# 8channelrelaydriver_smd.net
KiCad netlist of a schematic drawn in EAGLE
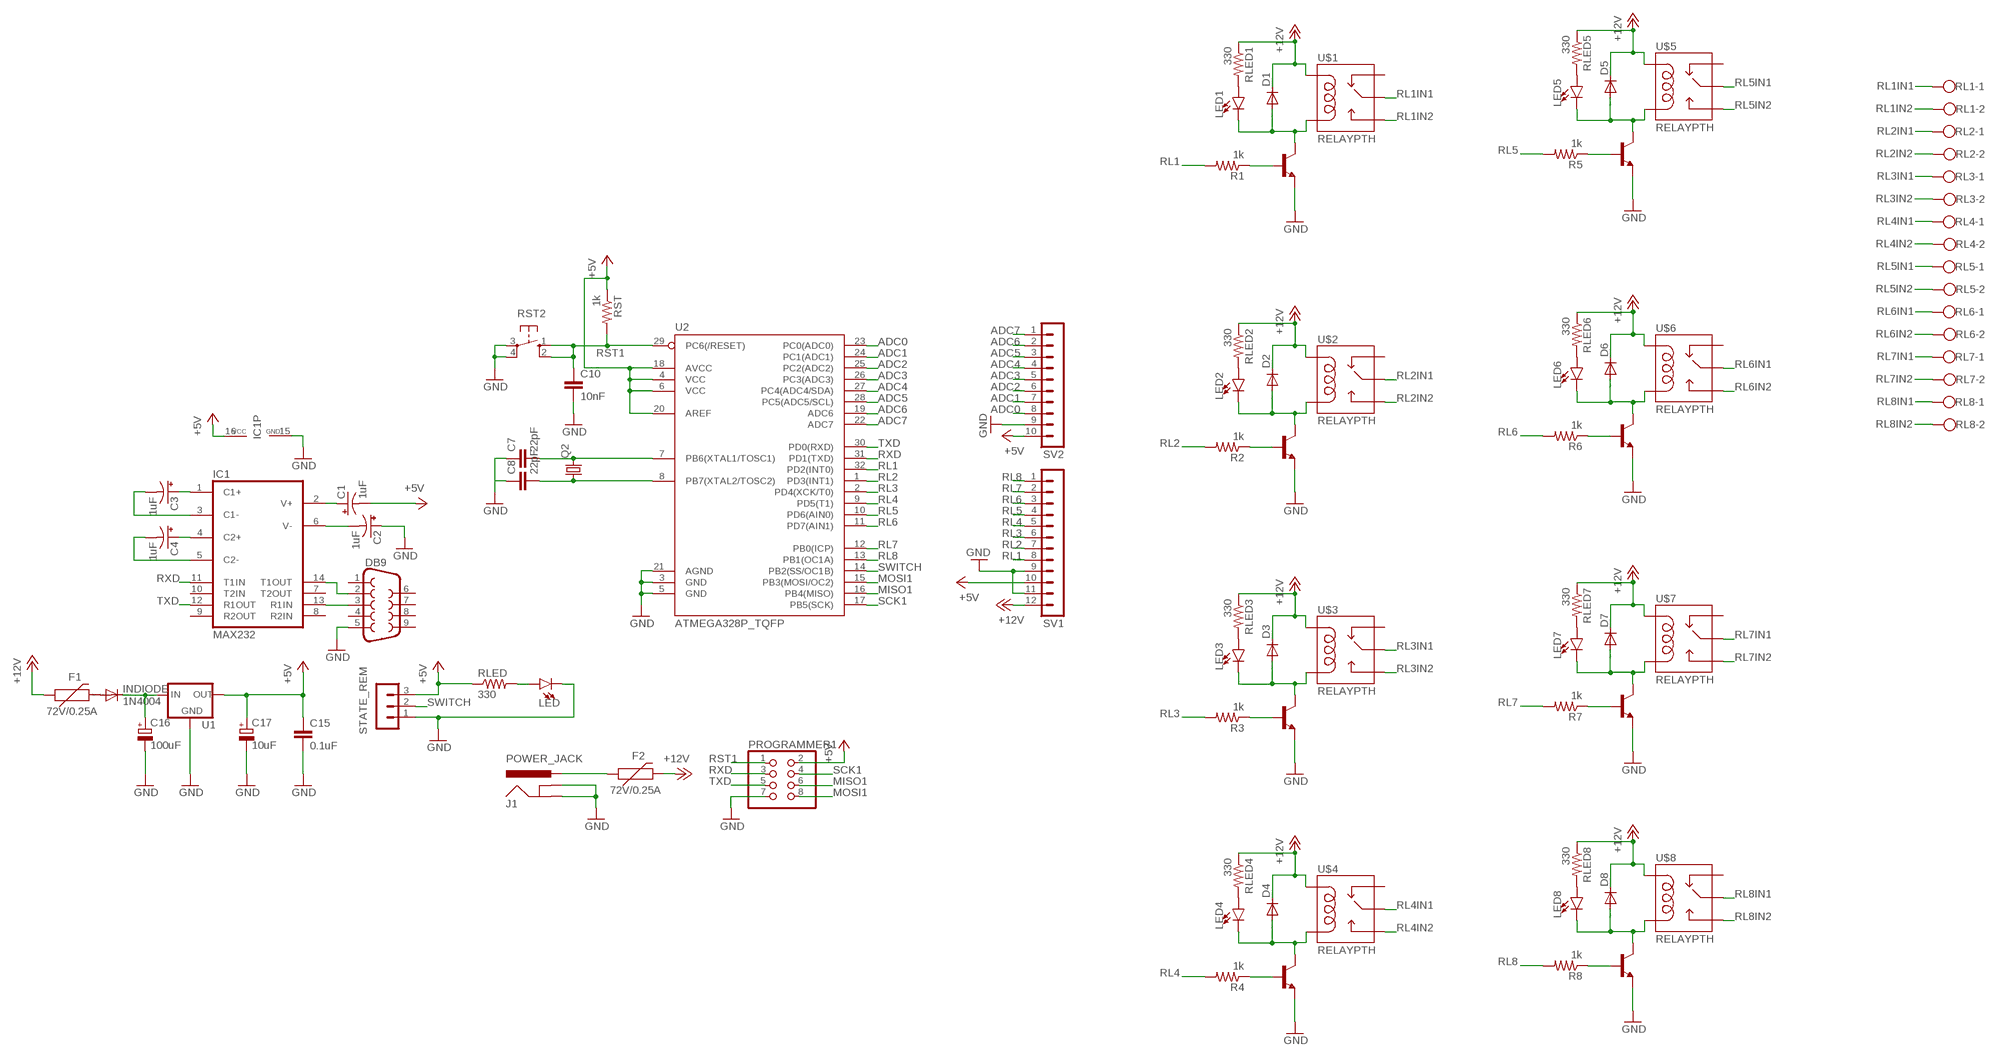
[diagram p0: schematic, sheet 1]

(export (version "E")
  (design (tool "Eeschema 10.0.6"))
  (components
    (comp (ref "C1")
      (value "1uF")
      (footprint "eagle-import:E2,5-6")
      (libsource (lib "eagle-import") (part "CPOL-USE2.5-6"))
    )
    (comp (ref "C2")
      (value "1uF")
      (footprint "eagle-import:E2,5-6")
      (libsource (lib "eagle-import") (part "CPOL-USE2.5-6"))
    )
    (comp (ref "C3")
      (value "1uF")
      (footprint "eagle-import:E2,5-6")
      (libsource (lib "eagle-import") (part "CPOL-USE2.5-6"))
    )
    (comp (ref "C4")
      (value "1uF")
      (footprint "eagle-import:E2,5-6")
      (libsource (lib "eagle-import") (part "CPOL-USE2.5-6"))
    )
    (comp (ref "C7")
      (value "22pF")
      (footprint "eagle-import:C1206")
      (libsource (lib "eagle-import") (part "C-EUC1206"))
    )
    (comp (ref "C8")
      (value "22pF")
      (footprint "eagle-import:C1206")
      (libsource (lib "eagle-import") (part "C-EUC1206"))
    )
    (comp (ref "C10")
      (value "10nF")
      (footprint "eagle-import:C1206")
      (libsource (lib "eagle-import") (part "C-EUC1206"))
    )
    (comp (ref "C15")
      (value "0.1uF")
      (footprint "eagle-import:C1206")
      (libsource (lib "eagle-import") (part "C-EUC1206"))
    )
    (comp (ref "C16")
      (value "100uF")
      (footprint "eagle-import:E2,5-6")
      (libsource (lib "eagle-import") (part "CPOL-EUE2.5-6"))
    )
    (comp (ref "C17")
      (value "10uF")
      (footprint "eagle-import:E2,5-6")
      (libsource (lib "eagle-import") (part "CPOL-EUE2.5-6"))
    )
    (comp (ref "D1")
      (value "1N4004")
      (footprint "eagle-import:DO41-10")
      (libsource (lib "eagle-import") (part "1N4004"))
    )
    (comp (ref "D2")
      (value "1N4004")
      (footprint "eagle-import:DO41-10")
      (libsource (lib "eagle-import") (part "1N4004"))
    )
    (comp (ref "D3")
      (value "1N4004")
      (footprint "eagle-import:DO41-10")
      (libsource (lib "eagle-import") (part "1N4004"))
    )
    (comp (ref "D4")
      (value "1N4004")
      (footprint "eagle-import:DO41-10")
      (libsource (lib "eagle-import") (part "1N4004"))
    )
    (comp (ref "D5")
      (value "1N4004")
      (footprint "eagle-import:DO41-10")
      (libsource (lib "eagle-import") (part "1N4004"))
    )
    (comp (ref "D6")
      (value "1N4004")
      (footprint "eagle-import:DO41-10")
      (libsource (lib "eagle-import") (part "1N4004"))
    )
    (comp (ref "D7")
      (value "1N4004")
      (footprint "eagle-import:DO41-10")
      (libsource (lib "eagle-import") (part "1N4004"))
    )
    (comp (ref "D8")
      (value "1N4004")
      (footprint "eagle-import:DO41-10")
      (libsource (lib "eagle-import") (part "1N4004"))
    )
    (comp (ref "DB9")
      (value "DB9FEMALE")
      (footprint "eagle-import:DB9")
      (libsource (lib "eagle-import") (part "DB9FEMALE"))
    )
    (comp (ref "F1")
      (value "72V/0.25A")
      (footprint "eagle-import:PTH")
      (libsource (lib "eagle-import") (part "PPTC_PTH"))
    )
    (comp (ref "F2")
      (value "72V/0.25A")
      (footprint "eagle-import:PTH")
      (libsource (lib "eagle-import") (part "PPTC_PTH"))
    )
    (comp (ref "IC1")
      (value "MAX232")
      (footprint "eagle-import:DIL16")
      (fields (field (name "MF") "MAXIM") (field (name "MPN") "MAX232ACPE+"))
      (libsource (lib "eagle-import") (part "MAX232"))
    )
    (comp (ref "INDIODE")
      (value "1N4004")
      (footprint "eagle-import:DO41-10")
      (libsource (lib "eagle-import") (part "1N4004"))
    )
    (comp (ref "J1")
      (value "POWER_JACK")
      (footprint "eagle-import:POWER_JACK_PTH")
      (libsource (lib "eagle-import") (part "POWER_JACK"))
    )
    (comp (ref "LED")
      (value "LED5MM")
      (footprint "eagle-import:LED_5MM")
      (libsource (lib "eagle-import") (part "LED5MM"))
    )
    (comp (ref "LED1")
      (value "LED5MM")
      (footprint "eagle-import:LED_5MM")
      (libsource (lib "eagle-import") (part "LED5MM"))
    )
    (comp (ref "LED2")
      (value "LED5MM")
      (footprint "eagle-import:LED_5MM")
      (libsource (lib "eagle-import") (part "LED5MM"))
    )
    (comp (ref "LED3")
      (value "LED5MM")
      (footprint "eagle-import:LED_5MM")
      (libsource (lib "eagle-import") (part "LED5MM"))
    )
    (comp (ref "LED4")
      (value "LED5MM")
      (footprint "eagle-import:LED_5MM")
      (libsource (lib "eagle-import") (part "LED5MM"))
    )
    (comp (ref "LED5")
      (value "LED5MM")
      (footprint "eagle-import:LED_5MM")
      (libsource (lib "eagle-import") (part "LED5MM"))
    )
    (comp (ref "LED6")
      (value "LED5MM")
      (footprint "eagle-import:LED_5MM")
      (libsource (lib "eagle-import") (part "LED5MM"))
    )
    (comp (ref "LED7")
      (value "LED5MM")
      (footprint "eagle-import:LED_5MM")
      (libsource (lib "eagle-import") (part "LED5MM"))
    )
    (comp (ref "LED8")
      (value "LED5MM")
      (footprint "eagle-import:LED_5MM")
      (libsource (lib "eagle-import") (part "LED5MM"))
    )
    (comp (ref "PROGRAMMER1")
      (value "PINHD-2X4")
      (footprint "eagle-import:2X04")
      (libsource (lib "eagle-import") (part "PINHD-2X4"))
    )
    (comp (ref "Q2")
      (value "CRYSTALHC49U70")
      (footprint "eagle-import:HC49U70")
      (libsource (lib "eagle-import") (part "CRYSTALHC49U70"))
    )
    (comp (ref "R1")
      (value "1k")
      (footprint "eagle-import:M1206")
      (libsource (lib "eagle-import") (part "R-US_M1206"))
    )
    (comp (ref "R2")
      (value "1k")
      (footprint "eagle-import:M1206")
      (libsource (lib "eagle-import") (part "R-US_M1206"))
    )
    (comp (ref "R3")
      (value "1k")
      (footprint "eagle-import:M1206")
      (libsource (lib "eagle-import") (part "R-US_M1206"))
    )
    (comp (ref "R4")
      (value "1k")
      (footprint "eagle-import:M1206")
      (libsource (lib "eagle-import") (part "R-US_M1206"))
    )
    (comp (ref "R5")
      (value "1k")
      (footprint "eagle-import:M1206")
      (libsource (lib "eagle-import") (part "R-US_M1206"))
    )
    (comp (ref "R6")
      (value "1k")
      (footprint "eagle-import:M1206")
      (libsource (lib "eagle-import") (part "R-US_M1206"))
    )
    (comp (ref "R7")
      (value "1k")
      (footprint "eagle-import:M1206")
      (libsource (lib "eagle-import") (part "R-US_M1206"))
    )
    (comp (ref "R8")
      (value "1k")
      (footprint "eagle-import:M1206")
      (libsource (lib "eagle-import") (part "R-US_M1206"))
    )
    (comp (ref "RL1")
      (value "W237-102")
      (footprint "eagle-import:W237-102")
      (fields (field (name "MPN") "237-102"))
      (libsource (lib "eagle-import") (part "W237-102"))
    )
    (comp (ref "RL2")
      (value "W237-102")
      (footprint "eagle-import:W237-102")
      (fields (field (name "MPN") "237-102"))
      (libsource (lib "eagle-import") (part "W237-102"))
    )
    (comp (ref "RL3")
      (value "W237-102")
      (footprint "eagle-import:W237-102")
      (fields (field (name "MPN") "237-102"))
      (libsource (lib "eagle-import") (part "W237-102"))
    )
    (comp (ref "RL4")
      (value "W237-102")
      (footprint "eagle-import:W237-102")
      (fields (field (name "MPN") "237-102"))
      (libsource (lib "eagle-import") (part "W237-102"))
    )
    (comp (ref "RL5")
      (value "W237-102")
      (footprint "eagle-import:W237-102")
      (fields (field (name "MPN") "237-102"))
      (libsource (lib "eagle-import") (part "W237-102"))
    )
    (comp (ref "RL6")
      (value "W237-102")
      (footprint "eagle-import:W237-102")
      (fields (field (name "MPN") "237-102"))
      (libsource (lib "eagle-import") (part "W237-102"))
    )
    (comp (ref "RL7")
      (value "W237-102")
      (footprint "eagle-import:W237-102")
      (fields (field (name "MPN") "237-102"))
      (libsource (lib "eagle-import") (part "W237-102"))
    )
    (comp (ref "RL8")
      (value "W237-102")
      (footprint "eagle-import:W237-102")
      (fields (field (name "MPN") "237-102"))
      (libsource (lib "eagle-import") (part "W237-102"))
    )
    (comp (ref "RLED")
      (value "330")
      (footprint "eagle-import:M1206")
      (libsource (lib "eagle-import") (part "R-US_M1206"))
    )
    (comp (ref "RLED1")
      (value "330")
      (footprint "eagle-import:M1206")
      (libsource (lib "eagle-import") (part "R-US_M1206"))
    )
    (comp (ref "RLED2")
      (value "330")
      (footprint "eagle-import:M1206")
      (libsource (lib "eagle-import") (part "R-US_M1206"))
    )
    (comp (ref "RLED3")
      (value "330")
      (footprint "eagle-import:M1206")
      (libsource (lib "eagle-import") (part "R-US_M1206"))
    )
    (comp (ref "RLED4")
      (value "330")
      (footprint "eagle-import:M1206")
      (libsource (lib "eagle-import") (part "R-US_M1206"))
    )
    (comp (ref "RLED5")
      (value "330")
      (footprint "eagle-import:M1206")
      (libsource (lib "eagle-import") (part "R-US_M1206"))
    )
    (comp (ref "RLED6")
      (value "330")
      (footprint "eagle-import:M1206")
      (libsource (lib "eagle-import") (part "R-US_M1206"))
    )
    (comp (ref "RLED7")
      (value "330")
      (footprint "eagle-import:M1206")
      (libsource (lib "eagle-import") (part "R-US_M1206"))
    )
    (comp (ref "RLED8")
      (value "330")
      (footprint "eagle-import:M1206")
      (libsource (lib "eagle-import") (part "R-US_M1206"))
    )
    (comp (ref "RST")
      (value "1k")
      (footprint "eagle-import:M1206")
      (libsource (lib "eagle-import") (part "R-US_M1206"))
    )
    (comp (ref "RST2")
      (value "10-XX")
      (footprint "eagle-import:B3F-10XX")
      (fields (field (name "MPN") "B3F-1000"))
      (libsource (lib "eagle-import") (part "10-XX"))
    )
    (comp (ref "STATE_REM")
      (value "MA03-1")
      (footprint "eagle-import:MA03-1")
      (libsource (lib "eagle-import") (part "MA03-1"))
    )
    (comp (ref "SV1")
      (value "MA12-1")
      (footprint "eagle-import:MA12-1")
      (libsource (lib "eagle-import") (part "MA12-1"))
    )
    (comp (ref "SV2")
      (value "MA10-1")
      (footprint "eagle-import:MA10-1")
      (libsource (lib "eagle-import") (part "MA10-1"))
    )
    (comp (ref "T1")
      (value "BC847")
      (footprint "eagle-import:SOT23")
      (libsource (lib "eagle-import") (part "BC847"))
    )
    (comp (ref "T2")
      (value "BC847")
      (footprint "eagle-import:SOT23")
      (libsource (lib "eagle-import") (part "BC847"))
    )
    (comp (ref "T3")
      (value "BC847")
      (footprint "eagle-import:SOT23")
      (libsource (lib "eagle-import") (part "BC847"))
    )
    (comp (ref "T4")
      (value "BC847")
      (footprint "eagle-import:SOT23")
      (libsource (lib "eagle-import") (part "BC847"))
    )
    (comp (ref "T5")
      (value "BC847")
      (footprint "eagle-import:SOT23")
      (libsource (lib "eagle-import") (part "BC847"))
    )
    (comp (ref "T6")
      (value "BC847")
      (footprint "eagle-import:SOT23")
      (libsource (lib "eagle-import") (part "BC847"))
    )
    (comp (ref "T7")
      (value "BC847")
      (footprint "eagle-import:SOT23")
      (libsource (lib "eagle-import") (part "BC847"))
    )
    (comp (ref "T8")
      (value "BC847")
      (footprint "eagle-import:SOT23")
      (libsource (lib "eagle-import") (part "BC847"))
    )
    (comp (ref "U$1")
      (value "RELAYPTH")
      (footprint "eagle-import:SRD-05VDC-SL-C")
      (libsource (lib "eagle-import") (part "RELAYPTH"))
    )
    (comp (ref "U$2")
      (value "RELAYPTH")
      (footprint "eagle-import:SRD-05VDC-SL-C")
      (libsource (lib "eagle-import") (part "RELAYPTH"))
    )
    (comp (ref "U$3")
      (value "RELAYPTH")
      (footprint "eagle-import:SRD-05VDC-SL-C")
      (libsource (lib "eagle-import") (part "RELAYPTH"))
    )
    (comp (ref "U$4")
      (value "RELAYPTH")
      (footprint "eagle-import:SRD-05VDC-SL-C")
      (libsource (lib "eagle-import") (part "RELAYPTH"))
    )
    (comp (ref "U$5")
      (value "RELAYPTH")
      (footprint "eagle-import:SRD-05VDC-SL-C")
      (libsource (lib "eagle-import") (part "RELAYPTH"))
    )
    (comp (ref "U$6")
      (value "RELAYPTH")
      (footprint "eagle-import:SRD-05VDC-SL-C")
      (libsource (lib "eagle-import") (part "RELAYPTH"))
    )
    (comp (ref "U$7")
      (value "RELAYPTH")
      (footprint "eagle-import:SRD-05VDC-SL-C")
      (libsource (lib "eagle-import") (part "RELAYPTH"))
    )
    (comp (ref "U$8")
      (value "RELAYPTH")
      (footprint "eagle-import:SRD-05VDC-SL-C")
      (libsource (lib "eagle-import") (part "RELAYPTH"))
    )
    (comp (ref "U1")
      (value "V_REG_78XXSIDE")
      (footprint "eagle-import:78XXL")
      (libsource (lib "eagle-import") (part "V_REG_78XXSIDE"))
    )
    (comp (ref "U2")
      (value "ATMEGA328P_TQFP")
      (footprint "eagle-import:TQFP32-08")
      (libsource (lib "eagle-import") (part "ATMEGA328P_TQFP"))
    )
  )
  (nets
    (net (code "1") (name "+5V") (class "Default")
      (node (ref "C1") (pin "-") (pinfunction "-_-") (pintype "passive"))
      (node (ref "C15") (pin "1") (pinfunction "1_1") (pintype "passive"))
      (node (ref "C17") (pin "+") (pinfunction "+_+") (pintype "passive"))
      (node (ref "IC1") (pin "16") (pinfunction "VCC_16") (pintype "power_in"))
      (node (ref "PROGRAMMER1") (pin "2") (pinfunction "2_2") (pintype "passive"))
      (node (ref "RLED") (pin "1") (pinfunction "1_1") (pintype "passive"))
      (node (ref "RST") (pin "1") (pinfunction "1_1") (pintype "passive"))
      (node (ref "STATE_REM") (pin "3") (pinfunction "3_3") (pintype "passive"))
      (node (ref "SV1") (pin "10") (pinfunction "10_10") (pintype "passive"))
      (node (ref "SV2") (pin "10") (pinfunction "10_10") (pintype "passive"))
      (node (ref "U1") (pin "OUT") (pinfunction "OUT_OUT") (pintype "passive"))
      (node (ref "U2") (pin "18") (pinfunction "AVCC_18") (pintype "bidirectional"))
      (node (ref "U2") (pin "20") (pinfunction "AREF_20") (pintype "bidirectional"))
      (node (ref "U2") (pin "4") (pinfunction "VCC_4") (pintype "bidirectional"))
      (node (ref "U2") (pin "6") (pinfunction "VCC_6") (pintype "bidirectional"))
    )
    (net (code "2") (name "+12V") (class "Default")
      (node (ref "D1") (pin "C") (pinfunction "C_C") (pintype "passive"))
      (node (ref "D2") (pin "C") (pinfunction "C_C") (pintype "passive"))
      (node (ref "D3") (pin "C") (pinfunction "C_C") (pintype "passive"))
      (node (ref "D4") (pin "C") (pinfunction "C_C") (pintype "passive"))
      (node (ref "D5") (pin "C") (pinfunction "C_C") (pintype "passive"))
      (node (ref "D6") (pin "C") (pinfunction "C_C") (pintype "passive"))
      (node (ref "D7") (pin "C") (pinfunction "C_C") (pintype "passive"))
      (node (ref "D8") (pin "C") (pinfunction "C_C") (pintype "passive"))
      (node (ref "F1") (pin "P$1") (pinfunction "1_P$1") (pintype "bidirectional"))
      (node (ref "F2") (pin "P$2") (pinfunction "2_P$2") (pintype "bidirectional"))
      (node (ref "RLED1") (pin "1") (pinfunction "1_1") (pintype "passive"))
      (node (ref "RLED2") (pin "1") (pinfunction "1_1") (pintype "passive"))
      (node (ref "RLED3") (pin "1") (pinfunction "1_1") (pintype "passive"))
      (node (ref "RLED4") (pin "1") (pinfunction "1_1") (pintype "passive"))
      (node (ref "RLED5") (pin "1") (pinfunction "1_1") (pintype "passive"))
      (node (ref "RLED6") (pin "1") (pinfunction "1_1") (pintype "passive"))
      (node (ref "RLED7") (pin "1") (pinfunction "1_1") (pintype "passive"))
      (node (ref "RLED8") (pin "1") (pinfunction "1_1") (pintype "passive"))
      (node (ref "SV1") (pin "12") (pinfunction "12_12") (pintype "passive"))
      (node (ref "U$1") (pin "COIL1") (pinfunction "COIL1_COIL1") (pintype "bidirectional"))
      (node (ref "U$2") (pin "COIL1") (pinfunction "COIL1_COIL1") (pintype "bidirectional"))
      (node (ref "U$3") (pin "COIL1") (pinfunction "COIL1_COIL1") (pintype "bidirectional"))
      (node (ref "U$4") (pin "COIL1") (pinfunction "COIL1_COIL1") (pintype "bidirectional"))
      (node (ref "U$5") (pin "COIL1") (pinfunction "COIL1_COIL1") (pintype "bidirectional"))
      (node (ref "U$6") (pin "COIL1") (pinfunction "COIL1_COIL1") (pintype "bidirectional"))
      (node (ref "U$7") (pin "COIL1") (pinfunction "COIL1_COIL1") (pintype "bidirectional"))
      (node (ref "U$8") (pin "COIL1") (pinfunction "COIL1_COIL1") (pintype "bidirectional"))
    )
    (net (code "3") (name "/ADC0") (class "Default")
      (node (ref "SV2") (pin "8") (pinfunction "8_8") (pintype "passive"))
      (node (ref "U2") (pin "23") (pinfunction "PC0(ADC0)_23") (pintype "bidirectional"))
    )
    (net (code "4") (name "/ADC1") (class "Default")
      (node (ref "SV2") (pin "7") (pinfunction "7_7") (pintype "passive"))
      (node (ref "U2") (pin "24") (pinfunction "PC1(ADC1)_24") (pintype "bidirectional"))
    )
    (net (code "5") (name "/ADC2") (class "Default")
      (node (ref "SV2") (pin "6") (pinfunction "6_6") (pintype "passive"))
      (node (ref "U2") (pin "25") (pinfunction "PC2(ADC2)_25") (pintype "bidirectional"))
    )
    (net (code "6") (name "/ADC3") (class "Default")
      (node (ref "SV2") (pin "5") (pinfunction "5_5") (pintype "passive"))
      (node (ref "U2") (pin "26") (pinfunction "PC3(ADC3)_26") (pintype "bidirectional"))
    )
    (net (code "7") (name "/ADC4") (class "Default")
      (node (ref "SV2") (pin "4") (pinfunction "4_4") (pintype "passive"))
      (node (ref "U2") (pin "27") (pinfunction "PC4(ADC4/SDA)_27") (pintype "bidirectional"))
    )
    (net (code "8") (name "/ADC5") (class "Default")
      (node (ref "SV2") (pin "3") (pinfunction "3_3") (pintype "passive"))
      (node (ref "U2") (pin "28") (pinfunction "PC5(ADC5/SCL)_28") (pintype "bidirectional"))
    )
    (net (code "9") (name "/ADC6") (class "Default")
      (node (ref "SV2") (pin "2") (pinfunction "2_2") (pintype "passive"))
      (node (ref "U2") (pin "19") (pinfunction "ADC6_19") (pintype "bidirectional"))
    )
    (net (code "10") (name "/ADC7") (class "Default")
      (node (ref "SV2") (pin "1") (pinfunction "1_1") (pintype "passive"))
      (node (ref "U2") (pin "22") (pinfunction "ADC7_22") (pintype "bidirectional"))
    )
    (net (code "11") (name "/MISO1") (class "Default")
      (node (ref "PROGRAMMER1") (pin "6") (pinfunction "6_6") (pintype "passive"))
      (node (ref "U2") (pin "16") (pinfunction "PB4(MISO)_16") (pintype "bidirectional"))
    )
    (net (code "12") (name "/MOSI1") (class "Default")
      (node (ref "PROGRAMMER1") (pin "8") (pinfunction "8_8") (pintype "passive"))
      (node (ref "U2") (pin "15") (pinfunction "PB3(MOSI/OC2)_15") (pintype "bidirectional"))
    )
    (net (code "13") (name "/RL1") (class "Default")
      (node (ref "R1") (pin "2") (pinfunction "2_2") (pintype "passive"))
      (node (ref "SV1") (pin "8") (pinfunction "8_8") (pintype "passive"))
      (node (ref "U2") (pin "32") (pinfunction "PD2(INT0)_32") (pintype "bidirectional"))
    )
    (net (code "14") (name "/RL1IN1") (class "Default")
      (node (ref "RL1") (pin "1") (pinfunction "KL_1") (pintype "passive"))
      (node (ref "U$1") (pin "SWCOMMON") (pinfunction "SWCOMMON_SWCOMMON") (pintype "bidirectional"))
    )
    (net (code "15") (name "/RL1IN2") (class "Default")
      (node (ref "RL1") (pin "2") (pinfunction "KL_2") (pintype "passive"))
      (node (ref "U$1") (pin "SWOPEN") (pinfunction "SWOPEN_SWOPEN") (pintype "bidirectional"))
    )
    (net (code "16") (name "/RL2") (class "Default")
      (node (ref "R2") (pin "2") (pinfunction "2_2") (pintype "passive"))
      (node (ref "SV1") (pin "7") (pinfunction "7_7") (pintype "passive"))
      (node (ref "U2") (pin "1") (pinfunction "PD3(INT1)_1") (pintype "bidirectional"))
    )
    (net (code "17") (name "/RL2IN1") (class "Default")
      (node (ref "RL2") (pin "1") (pinfunction "KL_1") (pintype "passive"))
      (node (ref "U$2") (pin "SWCOMMON") (pinfunction "SWCOMMON_SWCOMMON") (pintype "bidirectional"))
    )
    (net (code "18") (name "/RL2IN2") (class "Default")
      (node (ref "RL2") (pin "2") (pinfunction "KL_2") (pintype "passive"))
      (node (ref "U$2") (pin "SWOPEN") (pinfunction "SWOPEN_SWOPEN") (pintype "bidirectional"))
    )
    (net (code "19") (name "/RL3") (class "Default")
      (node (ref "R3") (pin "2") (pinfunction "2_2") (pintype "passive"))
      (node (ref "SV1") (pin "6") (pinfunction "6_6") (pintype "passive"))
      (node (ref "U2") (pin "2") (pinfunction "PD4(XCK/T0)_2") (pintype "bidirectional"))
    )
    (net (code "20") (name "/RL3IN1") (class "Default")
      (node (ref "RL3") (pin "1") (pinfunction "KL_1") (pintype "passive"))
      (node (ref "U$3") (pin "SWCOMMON") (pinfunction "SWCOMMON_SWCOMMON") (pintype "bidirectional"))
    )
    (net (code "21") (name "/RL3IN2") (class "Default")
      (node (ref "RL3") (pin "2") (pinfunction "KL_2") (pintype "passive"))
      (node (ref "U$3") (pin "SWOPEN") (pinfunction "SWOPEN_SWOPEN") (pintype "bidirectional"))
    )
    (net (code "22") (name "/RL4") (class "Default")
      (node (ref "R4") (pin "2") (pinfunction "2_2") (pintype "passive"))
      (node (ref "SV1") (pin "5") (pinfunction "5_5") (pintype "passive"))
      (node (ref "U2") (pin "9") (pinfunction "PD5(T1)_9") (pintype "bidirectional"))
    )
    (net (code "23") (name "/RL4IN1") (class "Default")
      (node (ref "RL4") (pin "1") (pinfunction "KL_1") (pintype "passive"))
      (node (ref "U$4") (pin "SWCOMMON") (pinfunction "SWCOMMON_SWCOMMON") (pintype "bidirectional"))
    )
    (net (code "24") (name "/RL4IN2") (class "Default")
      (node (ref "RL4") (pin "2") (pinfunction "KL_2") (pintype "passive"))
      (node (ref "U$4") (pin "SWOPEN") (pinfunction "SWOPEN_SWOPEN") (pintype "bidirectional"))
    )
    (net (code "25") (name "/RL5") (class "Default")
      (node (ref "R5") (pin "2") (pinfunction "2_2") (pintype "passive"))
      (node (ref "SV1") (pin "4") (pinfunction "4_4") (pintype "passive"))
      (node (ref "U2") (pin "10") (pinfunction "PD6(AIN0)_10") (pintype "bidirectional"))
    )
    (net (code "26") (name "/RL5IN1") (class "Default")
      (node (ref "RL5") (pin "1") (pinfunction "KL_1") (pintype "passive"))
      (node (ref "U$5") (pin "SWCOMMON") (pinfunction "SWCOMMON_SWCOMMON") (pintype "bidirectional"))
    )
    (net (code "27") (name "/RL5IN2") (class "Default")
      (node (ref "RL5") (pin "2") (pinfunction "KL_2") (pintype "passive"))
      (node (ref "U$5") (pin "SWOPEN") (pinfunction "SWOPEN_SWOPEN") (pintype "bidirectional"))
    )
    (net (code "28") (name "/RL6") (class "Default")
      (node (ref "R6") (pin "2") (pinfunction "2_2") (pintype "passive"))
      (node (ref "SV1") (pin "3") (pinfunction "3_3") (pintype "passive"))
      (node (ref "U2") (pin "11") (pinfunction "PD7(AIN1)_11") (pintype "bidirectional"))
    )
    (net (code "29") (name "/RL6IN1") (class "Default")
      (node (ref "RL6") (pin "1") (pinfunction "KL_1") (pintype "passive"))
      (node (ref "U$6") (pin "SWCOMMON") (pinfunction "SWCOMMON_SWCOMMON") (pintype "bidirectional"))
    )
    (net (code "30") (name "/RL6IN2") (class "Default")
      (node (ref "RL6") (pin "2") (pinfunction "KL_2") (pintype "passive"))
      (node (ref "U$6") (pin "SWOPEN") (pinfunction "SWOPEN_SWOPEN") (pintype "bidirectional"))
    )
    (net (code "31") (name "/RL7") (class "Default")
      (node (ref "R7") (pin "2") (pinfunction "2_2") (pintype "passive"))
      (node (ref "SV1") (pin "2") (pinfunction "2_2") (pintype "passive"))
      (node (ref "U2") (pin "12") (pinfunction "PB0(ICP)_12") (pintype "bidirectional"))
    )
    (net (code "32") (name "/RL7IN1") (class "Default")
      (node (ref "RL7") (pin "1") (pinfunction "KL_1") (pintype "passive"))
      (node (ref "U$7") (pin "SWCOMMON") (pinfunction "SWCOMMON_SWCOMMON") (pintype "bidirectional"))
    )
    (net (code "33") (name "/RL7IN2") (class "Default")
      (node (ref "RL7") (pin "2") (pinfunction "KL_2") (pintype "passive"))
      (node (ref "U$7") (pin "SWOPEN") (pinfunction "SWOPEN_SWOPEN") (pintype "bidirectional"))
    )
    (net (code "34") (name "/RL8") (class "Default")
      (node (ref "R8") (pin "2") (pinfunction "2_2") (pintype "passive"))
      (node (ref "SV1") (pin "1") (pinfunction "1_1") (pintype "passive"))
      (node (ref "U2") (pin "13") (pinfunction "PB1(OC1A)_13") (pintype "bidirectional"))
    )
    (net (code "35") (name "/RL8IN1") (class "Default")
      (node (ref "RL8") (pin "1") (pinfunction "KL_1") (pintype "passive"))
      (node (ref "U$8") (pin "SWCOMMON") (pinfunction "SWCOMMON_SWCOMMON") (pintype "bidirectional"))
    )
    (net (code "36") (name "/RL8IN2") (class "Default")
      (node (ref "RL8") (pin "2") (pinfunction "KL_2") (pintype "passive"))
      (node (ref "U$8") (pin "SWOPEN") (pinfunction "SWOPEN_SWOPEN") (pintype "bidirectional"))
    )
    (net (code "37") (name "/RST1") (class "Default")
      (node (ref "C10") (pin "1") (pinfunction "1_1") (pintype "passive"))
      (node (ref "PROGRAMMER1") (pin "1") (pinfunction "1_1") (pintype "passive"))
      (node (ref "RST") (pin "2") (pinfunction "2_2") (pintype "passive"))
      (node (ref "RST2") (pin "1") (pinfunction "S_1") (pintype "passive"))
      (node (ref "RST2") (pin "2") (pinfunction "S1_2") (pintype "passive"))
      (node (ref "U2") (pin "29") (pinfunction "PC6(/RESET)_29") (pintype "bidirectional"))
    )
    (net (code "38") (name "/RXD") (class "Default")
      (node (ref "IC1") (pin "11") (pinfunction "T1IN_11") (pintype "input"))
      (node (ref "PROGRAMMER1") (pin "3") (pinfunction "3_3") (pintype "passive"))
      (node (ref "U2") (pin "31") (pinfunction "PD1(TXD)_31") (pintype "bidirectional"))
    )
    (net (code "39") (name "/SCK1") (class "Default")
      (node (ref "PROGRAMMER1") (pin "4") (pinfunction "4_4") (pintype "passive"))
      (node (ref "U2") (pin "17") (pinfunction "PB5(SCK)_17") (pintype "bidirectional"))
    )
    (net (code "40") (name "/SWITCH") (class "Default")
      (node (ref "STATE_REM") (pin "2") (pinfunction "2_2") (pintype "passive"))
      (node (ref "U2") (pin "14") (pinfunction "PB2(SS/OC1B)_14") (pintype "bidirectional"))
    )
    (net (code "41") (name "/TXD") (class "Default")
      (node (ref "IC1") (pin "12") (pinfunction "R1OUT_12") (pintype "output"))
      (node (ref "PROGRAMMER1") (pin "5") (pinfunction "5_5") (pintype "passive"))
      (node (ref "U2") (pin "30") (pinfunction "PD0(RXD)_30") (pintype "bidirectional"))
    )
    (net (code "42") (name "GND") (class "Default")
      (node (ref "C10") (pin "2") (pinfunction "2_2") (pintype "passive"))
      (node (ref "C15") (pin "2") (pinfunction "2_2") (pintype "passive"))
      (node (ref "C16") (pin "-") (pinfunction "-_-") (pintype "passive"))
      (node (ref "C17") (pin "-") (pinfunction "-_-") (pintype "passive"))
      (node (ref "C2") (pin "+") (pinfunction "+_+") (pintype "passive"))
      (node (ref "C7") (pin "1") (pinfunction "1_1") (pintype "passive"))
      (node (ref "C8") (pin "1") (pinfunction "1_1") (pintype "passive"))
      (node (ref "DB9") (pin "5") (pinfunction "5_5") (pintype "passive"))
      (node (ref "IC1") (pin "15") (pinfunction "GND_15") (pintype "power_in"))
      (node (ref "J1") (pin "GND") (pinfunction "GND_GND") (pintype "bidirectional"))
      (node (ref "J1") (pin "GNDBREAK") (pinfunction "GNDBREAK_GNDBREAK") (pintype "bidirectional"))
      (node (ref "LED") (pin "K") (pinfunction "C_K") (pintype "passive"))
      (node (ref "PROGRAMMER1") (pin "7") (pinfunction "7_7") (pintype "passive"))
      (node (ref "RST2") (pin "3") (pinfunction "P_3") (pintype "passive"))
      (node (ref "RST2") (pin "4") (pinfunction "P1_4") (pintype "passive"))
      (node (ref "STATE_REM") (pin "1") (pinfunction "1_1") (pintype "passive"))
      (node (ref "SV1") (pin "11") (pinfunction "11_11") (pintype "passive"))
      (node (ref "SV1") (pin "9") (pinfunction "9_9") (pintype "passive"))
      (node (ref "SV2") (pin "9") (pinfunction "9_9") (pintype "passive"))
      (node (ref "T1") (pin "2") (pinfunction "E_2") (pintype "passive"))
      (node (ref "T2") (pin "2") (pinfunction "E_2") (pintype "passive"))
      (node (ref "T3") (pin "2") (pinfunction "E_2") (pintype "passive"))
      (node (ref "T4") (pin "2") (pinfunction "E_2") (pintype "passive"))
      (node (ref "T5") (pin "2") (pinfunction "E_2") (pintype "passive"))
      (node (ref "T6") (pin "2") (pinfunction "E_2") (pintype "passive"))
      (node (ref "T7") (pin "2") (pinfunction "E_2") (pintype "passive"))
      (node (ref "T8") (pin "2") (pinfunction "E_2") (pintype "passive"))
      (node (ref "U1") (pin "GND") (pinfunction "GND_GND") (pintype "input"))
      (node (ref "U2") (pin "21") (pinfunction "AGND_21") (pintype "bidirectional"))
      (node (ref "U2") (pin "3") (pinfunction "GND_3") (pintype "bidirectional"))
      (node (ref "U2") (pin "5") (pinfunction "GND_5") (pintype "bidirectional"))
    )
    (net (code "43") (name "Net-(C16-Pad+)") (class "Default")
      (node (ref "C16") (pin "+") (pinfunction "+_+") (pintype "passive"))
      (node (ref "INDIODE") (pin "C") (pinfunction "C_C") (pintype "passive"))
      (node (ref "U1") (pin "IN") (pinfunction "IN_IN") (pintype "input"))
    )
    (net (code "44") (name "Net-(F1-2)") (class "Default")
      (node (ref "F1") (pin "P$2") (pinfunction "2_P$2") (pintype "bidirectional"))
      (node (ref "INDIODE") (pin "A") (pinfunction "A_A") (pintype "passive"))
    )
    (net (code "45") (name "Net-(F2-1)") (class "Default")
      (node (ref "F2") (pin "P$1") (pinfunction "1_P$1") (pintype "bidirectional"))
      (node (ref "J1") (pin "PWR") (pinfunction "PWR_PWR") (pintype "bidirectional"))
    )
    (net (code "46") (name "Net-(IC1A-C1+)") (class "Default")
      (node (ref "C3") (pin "+") (pinfunction "+_+") (pintype "passive"))
      (node (ref "IC1") (pin "1") (pinfunction "C1+_1") (pintype "bidirectional"))
    )
    (net (code "47") (name "Net-(IC1A-C1-)") (class "Default")
      (node (ref "C3") (pin "-") (pinfunction "-_-") (pintype "passive"))
      (node (ref "IC1") (pin "3") (pinfunction "C1-_3") (pintype "bidirectional"))
    )
    (net (code "48") (name "Net-(IC1A-C2+)") (class "Default")
      (node (ref "C4") (pin "+") (pinfunction "+_+") (pintype "passive"))
      (node (ref "IC1") (pin "4") (pinfunction "C2+_4") (pintype "bidirectional"))
    )
    (net (code "49") (name "Net-(IC1A-C2-)") (class "Default")
      (node (ref "C4") (pin "-") (pinfunction "-_-") (pintype "passive"))
      (node (ref "IC1") (pin "5") (pinfunction "C2-_5") (pintype "bidirectional"))
    )
    (net (code "50") (name "Net-(IC1A-R1IN)") (class "Default")
      (node (ref "DB9") (pin "3") (pinfunction "3_3") (pintype "passive"))
      (node (ref "IC1") (pin "13") (pinfunction "R1IN_13") (pintype "input"))
    )
    (net (code "51") (name "Net-(IC1A-T1OUT)") (class "Default")
      (node (ref "DB9") (pin "2") (pinfunction "2_2") (pintype "passive"))
      (node (ref "IC1") (pin "14") (pinfunction "T1OUT_14") (pintype "output"))
    )
    (net (code "52") (name "Net-(IC1A-V+)") (class "Default")
      (node (ref "C1") (pin "+") (pinfunction "+_+") (pintype "passive"))
      (node (ref "IC1") (pin "2") (pinfunction "V+_2") (pintype "bidirectional"))
    )
    (net (code "53") (name "Net-(IC1A-V-)") (class "Default")
      (node (ref "C2") (pin "-") (pinfunction "-_-") (pintype "passive"))
      (node (ref "IC1") (pin "6") (pinfunction "V-_6") (pintype "bidirectional"))
    )
    (net (code "54") (name "Net-(LED-PadA)") (class "Default")
      (node (ref "LED") (pin "A") (pinfunction "A_A") (pintype "passive"))
      (node (ref "RLED") (pin "2") (pinfunction "2_2") (pintype "passive"))
    )
    (net (code "55") (name "Net-(LED1-C)") (class "Default")
      (node (ref "D1") (pin "A") (pinfunction "A_A") (pintype "passive"))
      (node (ref "LED1") (pin "K") (pinfunction "C_K") (pintype "passive"))
      (node (ref "T1") (pin "3") (pinfunction "C_3") (pintype "passive"))
      (node (ref "U$1") (pin "COIL0") (pinfunction "COIL0_COIL0") (pintype "bidirectional"))
    )
    (net (code "56") (name "Net-(LED1-PadA)") (class "Default")
      (node (ref "LED1") (pin "A") (pinfunction "A_A") (pintype "passive"))
      (node (ref "RLED1") (pin "2") (pinfunction "2_2") (pintype "passive"))
    )
    (net (code "57") (name "Net-(LED2-C)") (class "Default")
      (node (ref "D2") (pin "A") (pinfunction "A_A") (pintype "passive"))
      (node (ref "LED2") (pin "K") (pinfunction "C_K") (pintype "passive"))
      (node (ref "T2") (pin "3") (pinfunction "C_3") (pintype "passive"))
      (node (ref "U$2") (pin "COIL0") (pinfunction "COIL0_COIL0") (pintype "bidirectional"))
    )
    (net (code "58") (name "Net-(LED2-PadA)") (class "Default")
      (node (ref "LED2") (pin "A") (pinfunction "A_A") (pintype "passive"))
      (node (ref "RLED2") (pin "2") (pinfunction "2_2") (pintype "passive"))
    )
    (net (code "59") (name "Net-(LED3-C)") (class "Default")
      (node (ref "D3") (pin "A") (pinfunction "A_A") (pintype "passive"))
      (node (ref "LED3") (pin "K") (pinfunction "C_K") (pintype "passive"))
      (node (ref "T3") (pin "3") (pinfunction "C_3") (pintype "passive"))
      (node (ref "U$3") (pin "COIL0") (pinfunction "COIL0_COIL0") (pintype "bidirectional"))
    )
    (net (code "60") (name "Net-(LED3-PadA)") (class "Default")
      (node (ref "LED3") (pin "A") (pinfunction "A_A") (pintype "passive"))
      (node (ref "RLED3") (pin "2") (pinfunction "2_2") (pintype "passive"))
    )
    (net (code "61") (name "Net-(LED4-C)") (class "Default")
      (node (ref "D4") (pin "A") (pinfunction "A_A") (pintype "passive"))
      (node (ref "LED4") (pin "K") (pinfunction "C_K") (pintype "passive"))
      (node (ref "T4") (pin "3") (pinfunction "C_3") (pintype "passive"))
      (node (ref "U$4") (pin "COIL0") (pinfunction "COIL0_COIL0") (pintype "bidirectional"))
    )
    (net (code "62") (name "Net-(LED4-PadA)") (class "Default")
      (node (ref "LED4") (pin "A") (pinfunction "A_A") (pintype "passive"))
      (node (ref "RLED4") (pin "2") (pinfunction "2_2") (pintype "passive"))
    )
    (net (code "63") (name "Net-(LED5-C)") (class "Default")
      (node (ref "D5") (pin "A") (pinfunction "A_A") (pintype "passive"))
      (node (ref "LED5") (pin "K") (pinfunction "C_K") (pintype "passive"))
      (node (ref "T5") (pin "3") (pinfunction "C_3") (pintype "passive"))
      (node (ref "U$5") (pin "COIL0") (pinfunction "COIL0_COIL0") (pintype "bidirectional"))
    )
    (net (code "64") (name "Net-(LED5-PadA)") (class "Default")
      (node (ref "LED5") (pin "A") (pinfunction "A_A") (pintype "passive"))
      (node (ref "RLED5") (pin "2") (pinfunction "2_2") (pintype "passive"))
    )
    (net (code "65") (name "Net-(LED6-C)") (class "Default")
      (node (ref "D6") (pin "A") (pinfunction "A_A") (pintype "passive"))
      (node (ref "LED6") (pin "K") (pinfunction "C_K") (pintype "passive"))
      (node (ref "T6") (pin "3") (pinfunction "C_3") (pintype "passive"))
      (node (ref "U$6") (pin "COIL0") (pinfunction "COIL0_COIL0") (pintype "bidirectional"))
    )
    (net (code "66") (name "Net-(LED6-PadA)") (class "Default")
      (node (ref "LED6") (pin "A") (pinfunction "A_A") (pintype "passive"))
      (node (ref "RLED6") (pin "2") (pinfunction "2_2") (pintype "passive"))
    )
    (net (code "67") (name "Net-(LED7-C)") (class "Default")
      (node (ref "D7") (pin "A") (pinfunction "A_A") (pintype "passive"))
      (node (ref "LED7") (pin "K") (pinfunction "C_K") (pintype "passive"))
      (node (ref "T7") (pin "3") (pinfunction "C_3") (pintype "passive"))
      (node (ref "U$7") (pin "COIL0") (pinfunction "COIL0_COIL0") (pintype "bidirectional"))
    )
    (net (code "68") (name "Net-(LED7-PadA)") (class "Default")
      (node (ref "LED7") (pin "A") (pinfunction "A_A") (pintype "passive"))
      (node (ref "RLED7") (pin "2") (pinfunction "2_2") (pintype "passive"))
    )
    (net (code "69") (name "Net-(LED8-C)") (class "Default")
      (node (ref "D8") (pin "A") (pinfunction "A_A") (pintype "passive"))
      (node (ref "LED8") (pin "K") (pinfunction "C_K") (pintype "passive"))
      (node (ref "T8") (pin "3") (pinfunction "C_3") (pintype "passive"))
      (node (ref "U$8") (pin "COIL0") (pinfunction "COIL0_COIL0") (pintype "bidirectional"))
    )
    (net (code "70") (name "Net-(LED8-PadA)") (class "Default")
      (node (ref "LED8") (pin "A") (pinfunction "A_A") (pintype "passive"))
      (node (ref "RLED8") (pin "2") (pinfunction "2_2") (pintype "passive"))
    )
    (net (code "71") (name "Net-(T1-B)") (class "Default")
      (node (ref "R1") (pin "1") (pinfunction "1_1") (pintype "passive"))
      (node (ref "T1") (pin "1") (pinfunction "B_1") (pintype "passive"))
    )
    (net (code "72") (name "Net-(T2-B)") (class "Default")
      (node (ref "R2") (pin "1") (pinfunction "1_1") (pintype "passive"))
      (node (ref "T2") (pin "1") (pinfunction "B_1") (pintype "passive"))
    )
    (net (code "73") (name "Net-(T3-B)") (class "Default")
      (node (ref "R3") (pin "1") (pinfunction "1_1") (pintype "passive"))
      (node (ref "T3") (pin "1") (pinfunction "B_1") (pintype "passive"))
    )
    (net (code "74") (name "Net-(T4-B)") (class "Default")
      (node (ref "R4") (pin "1") (pinfunction "1_1") (pintype "passive"))
      (node (ref "T4") (pin "1") (pinfunction "B_1") (pintype "passive"))
    )
    (net (code "75") (name "Net-(T5-B)") (class "Default")
      (node (ref "R5") (pin "1") (pinfunction "1_1") (pintype "passive"))
      (node (ref "T5") (pin "1") (pinfunction "B_1") (pintype "passive"))
    )
    (net (code "76") (name "Net-(T6-B)") (class "Default")
      (node (ref "R6") (pin "1") (pinfunction "1_1") (pintype "passive"))
      (node (ref "T6") (pin "1") (pinfunction "B_1") (pintype "passive"))
    )
    (net (code "77") (name "Net-(T7-B)") (class "Default")
      (node (ref "R7") (pin "1") (pinfunction "1_1") (pintype "passive"))
      (node (ref "T7") (pin "1") (pinfunction "B_1") (pintype "passive"))
    )
    (net (code "78") (name "Net-(T8-B)") (class "Default")
      (node (ref "R8") (pin "1") (pinfunction "1_1") (pintype "passive"))
      (node (ref "T8") (pin "1") (pinfunction "B_1") (pintype "passive"))
    )
    (net (code "79") (name "Net-(U2-PB6(XTAL1{slash}TOSC1))") (class "Default")
      (node (ref "C7") (pin "2") (pinfunction "2_2") (pintype "passive"))
      (node (ref "Q2") (pin "2") (pinfunction "2_2") (pintype "passive"))
      (node (ref "U2") (pin "7") (pinfunction "PB6(XTAL1/TOSC1)_7") (pintype "bidirectional"))
    )
    (net (code "80") (name "Net-(U2-PB7(XTAL2{slash}TOSC2))") (class "Default")
      (node (ref "C8") (pin "2") (pinfunction "2_2") (pintype "passive"))
      (node (ref "Q2") (pin "1") (pinfunction "1_1") (pintype "passive"))
      (node (ref "U2") (pin "8") (pinfunction "PB7(XTAL2/TOSC2)_8") (pintype "bidirectional"))
    )
    (net (code "81") (name "unconnected-(DB9-Pad1)") (class "Default")
      (node (ref "DB9") (pin "1") (pinfunction "1_1") (pintype "passive"))
    )
    (net (code "82") (name "unconnected-(DB9-Pad4)") (class "Default")
      (node (ref "DB9") (pin "4") (pinfunction "4_4") (pintype "passive"))
    )
    (net (code "83") (name "unconnected-(DB9-Pad6)") (class "Default")
      (node (ref "DB9") (pin "6") (pinfunction "6_6") (pintype "passive"))
    )
    (net (code "84") (name "unconnected-(DB9-Pad7)") (class "Default")
      (node (ref "DB9") (pin "7") (pinfunction "7_7") (pintype "passive"))
    )
    (net (code "85") (name "unconnected-(DB9-Pad8)") (class "Default")
      (node (ref "DB9") (pin "8") (pinfunction "8_8") (pintype "passive"))
    )
    (net (code "86") (name "unconnected-(DB9-Pad9)") (class "Default")
      (node (ref "DB9") (pin "9") (pinfunction "9_9") (pintype "passive"))
    )
    (net (code "87") (name "unconnected-(IC1A-R2IN-Pad8)") (class "Default")
      (node (ref "IC1") (pin "8") (pinfunction "R2IN_8") (pintype "input"))
    )
    (net (code "88") (name "unconnected-(IC1A-R2OUT-Pad9)") (class "Default")
      (node (ref "IC1") (pin "9") (pinfunction "R2OUT_9") (pintype "output"))
    )
    (net (code "89") (name "unconnected-(IC1A-T2IN-Pad10)") (class "Default")
      (node (ref "IC1") (pin "10") (pinfunction "T2IN_10") (pintype "input"))
    )
    (net (code "90") (name "unconnected-(IC1A-T2OUT-Pad7)") (class "Default")
      (node (ref "IC1") (pin "7") (pinfunction "T2OUT_7") (pintype "output"))
    )
    (net (code "91") (name "unconnected-(U$1-SWCLOSE-PadSWCLOSED)") (class "Default")
      (node (ref "U$1") (pin "SWCLOSED") (pinfunction "SWCLOSE_SWCLOSED") (pintype "bidirectional"))
    )
    (net (code "92") (name "unconnected-(U$2-SWCLOSE-PadSWCLOSED)") (class "Default")
      (node (ref "U$2") (pin "SWCLOSED") (pinfunction "SWCLOSE_SWCLOSED") (pintype "bidirectional"))
    )
    (net (code "93") (name "unconnected-(U$3-SWCLOSE-PadSWCLOSED)") (class "Default")
      (node (ref "U$3") (pin "SWCLOSED") (pinfunction "SWCLOSE_SWCLOSED") (pintype "bidirectional"))
    )
    (net (code "94") (name "unconnected-(U$4-SWCLOSE-PadSWCLOSED)") (class "Default")
      (node (ref "U$4") (pin "SWCLOSED") (pinfunction "SWCLOSE_SWCLOSED") (pintype "bidirectional"))
    )
    (net (code "95") (name "unconnected-(U$5-SWCLOSE-PadSWCLOSED)") (class "Default")
      (node (ref "U$5") (pin "SWCLOSED") (pinfunction "SWCLOSE_SWCLOSED") (pintype "bidirectional"))
    )
    (net (code "96") (name "unconnected-(U$6-SWCLOSE-PadSWCLOSED)") (class "Default")
      (node (ref "U$6") (pin "SWCLOSED") (pinfunction "SWCLOSE_SWCLOSED") (pintype "bidirectional"))
    )
    (net (code "97") (name "unconnected-(U$7-SWCLOSE-PadSWCLOSED)") (class "Default")
      (node (ref "U$7") (pin "SWCLOSED") (pinfunction "SWCLOSE_SWCLOSED") (pintype "bidirectional"))
    )
    (net (code "98") (name "unconnected-(U$8-SWCLOSE-PadSWCLOSED)") (class "Default")
      (node (ref "U$8") (pin "SWCLOSED") (pinfunction "SWCLOSE_SWCLOSED") (pintype "bidirectional"))
    )
  )
)
